# l4.net
KiCad netlist of a schematic drawn in Altium Designer
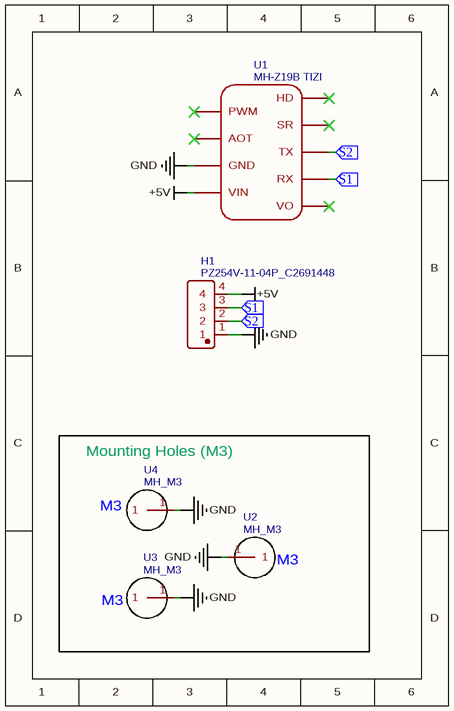
[diagram p0: l4.schdoc]

(export (version "E")
  (design (tool "Eeschema 10.0.6"))
  (components
    (comp (ref "H1")
      (value "PZ254V-11-04P_C2691448")
      (fields
        (field (name "MANUFACTURER") "XFCN(兴飞)")
        (field (name "MANUFACTURER PART") "PZ254V-11-04P")
        (field (name "CONTRIBUTOR") "LCSC")
      )
      (libsource (lib "altium-import") (part "root_2_PZ254V-11-04P_C2691448_"))
    )
    (comp (ref "U1")
      (value "MH-Z19B TIZI")
      (fields (field (name "CONTRIBUTOR") "tiziano8923"))
      (libsource (lib "altium-import") (part "root_0_MH-Z19B TIZI_"))
    )
    (comp (ref "U2")
      (value "MH_M3")
      (fields (field (name "CONTRIBUTOR") "js314dev"))
      (libsource (lib "altium-import") (part "root_2_MH_M3_"))
    )
    (comp (ref "U3")
      (value "MH_M3")
      (fields (field (name "CONTRIBUTOR") "js314dev"))
      (libsource (lib "altium-import") (part "root_0_MH_M3_"))
    )
    (comp (ref "U4")
      (value "MH_M3")
      (fields (field (name "CONTRIBUTOR") "js314dev"))
      (libsource (lib "altium-import") (part "root_0_MH_M3_"))
    )
  )
  (nets
    (net (code "1") (name "+5V") (class "Default")
      (node (ref "H1") (pin "4") (pinfunction "4_4") (pintype "passive"))
      (node (ref "U1") (pin "6") (pinfunction "VIN_6") (pintype "passive"))
    )
    (net (code "2") (name "/S1") (class "Default")
      (node (ref "H1") (pin "3") (pinfunction "3_3") (pintype "passive"))
      (node (ref "U1") (pin "2") (pinfunction "RX_2") (pintype "passive"))
    )
    (net (code "3") (name "/S2") (class "Default")
      (node (ref "H1") (pin "2") (pinfunction "2_2") (pintype "passive"))
      (node (ref "U1") (pin "3") (pinfunction "TX_3") (pintype "passive"))
    )
    (net (code "4") (name "GND") (class "Default")
      (node (ref "H1") (pin "1") (pinfunction "1_1") (pintype "passive"))
      (node (ref "U1") (pin "7") (pinfunction "GND_7") (pintype "passive"))
      (node (ref "U2") (pin "1") (pinfunction "1_1") (pintype "passive"))
      (node (ref "U3") (pin "1") (pinfunction "1_1") (pintype "passive"))
      (node (ref "U4") (pin "1") (pinfunction "1_1") (pintype "passive"))
    )
    (net (code "5") (name "unconnected-(U1-AOT-Pad8)") (class "Default")
      (node (ref "U1") (pin "8") (pinfunction "AOT_8") (pintype "passive+no_connect"))
    )
    (net (code "6") (name "unconnected-(U1-HD-Pad5)") (class "Default")
      (node (ref "U1") (pin "5") (pinfunction "HD_5") (pintype "passive+no_connect"))
    )
    (net (code "7") (name "unconnected-(U1-PWM-Pad9)") (class "Default")
      (node (ref "U1") (pin "9") (pinfunction "PWM_9") (pintype "passive+no_connect"))
    )
    (net (code "8") (name "unconnected-(U1-SR-Pad4)") (class "Default")
      (node (ref "U1") (pin "4") (pinfunction "SR_4") (pintype "passive+no_connect"))
    )
    (net (code "9") (name "unconnected-(U1-VO-Pad1)") (class "Default")
      (node (ref "U1") (pin "1") (pinfunction "VO_1") (pintype "passive+no_connect"))
    )
  )
)
